# s16_panel_1.net
KiCad netlist of a schematic drawn in EAGLE
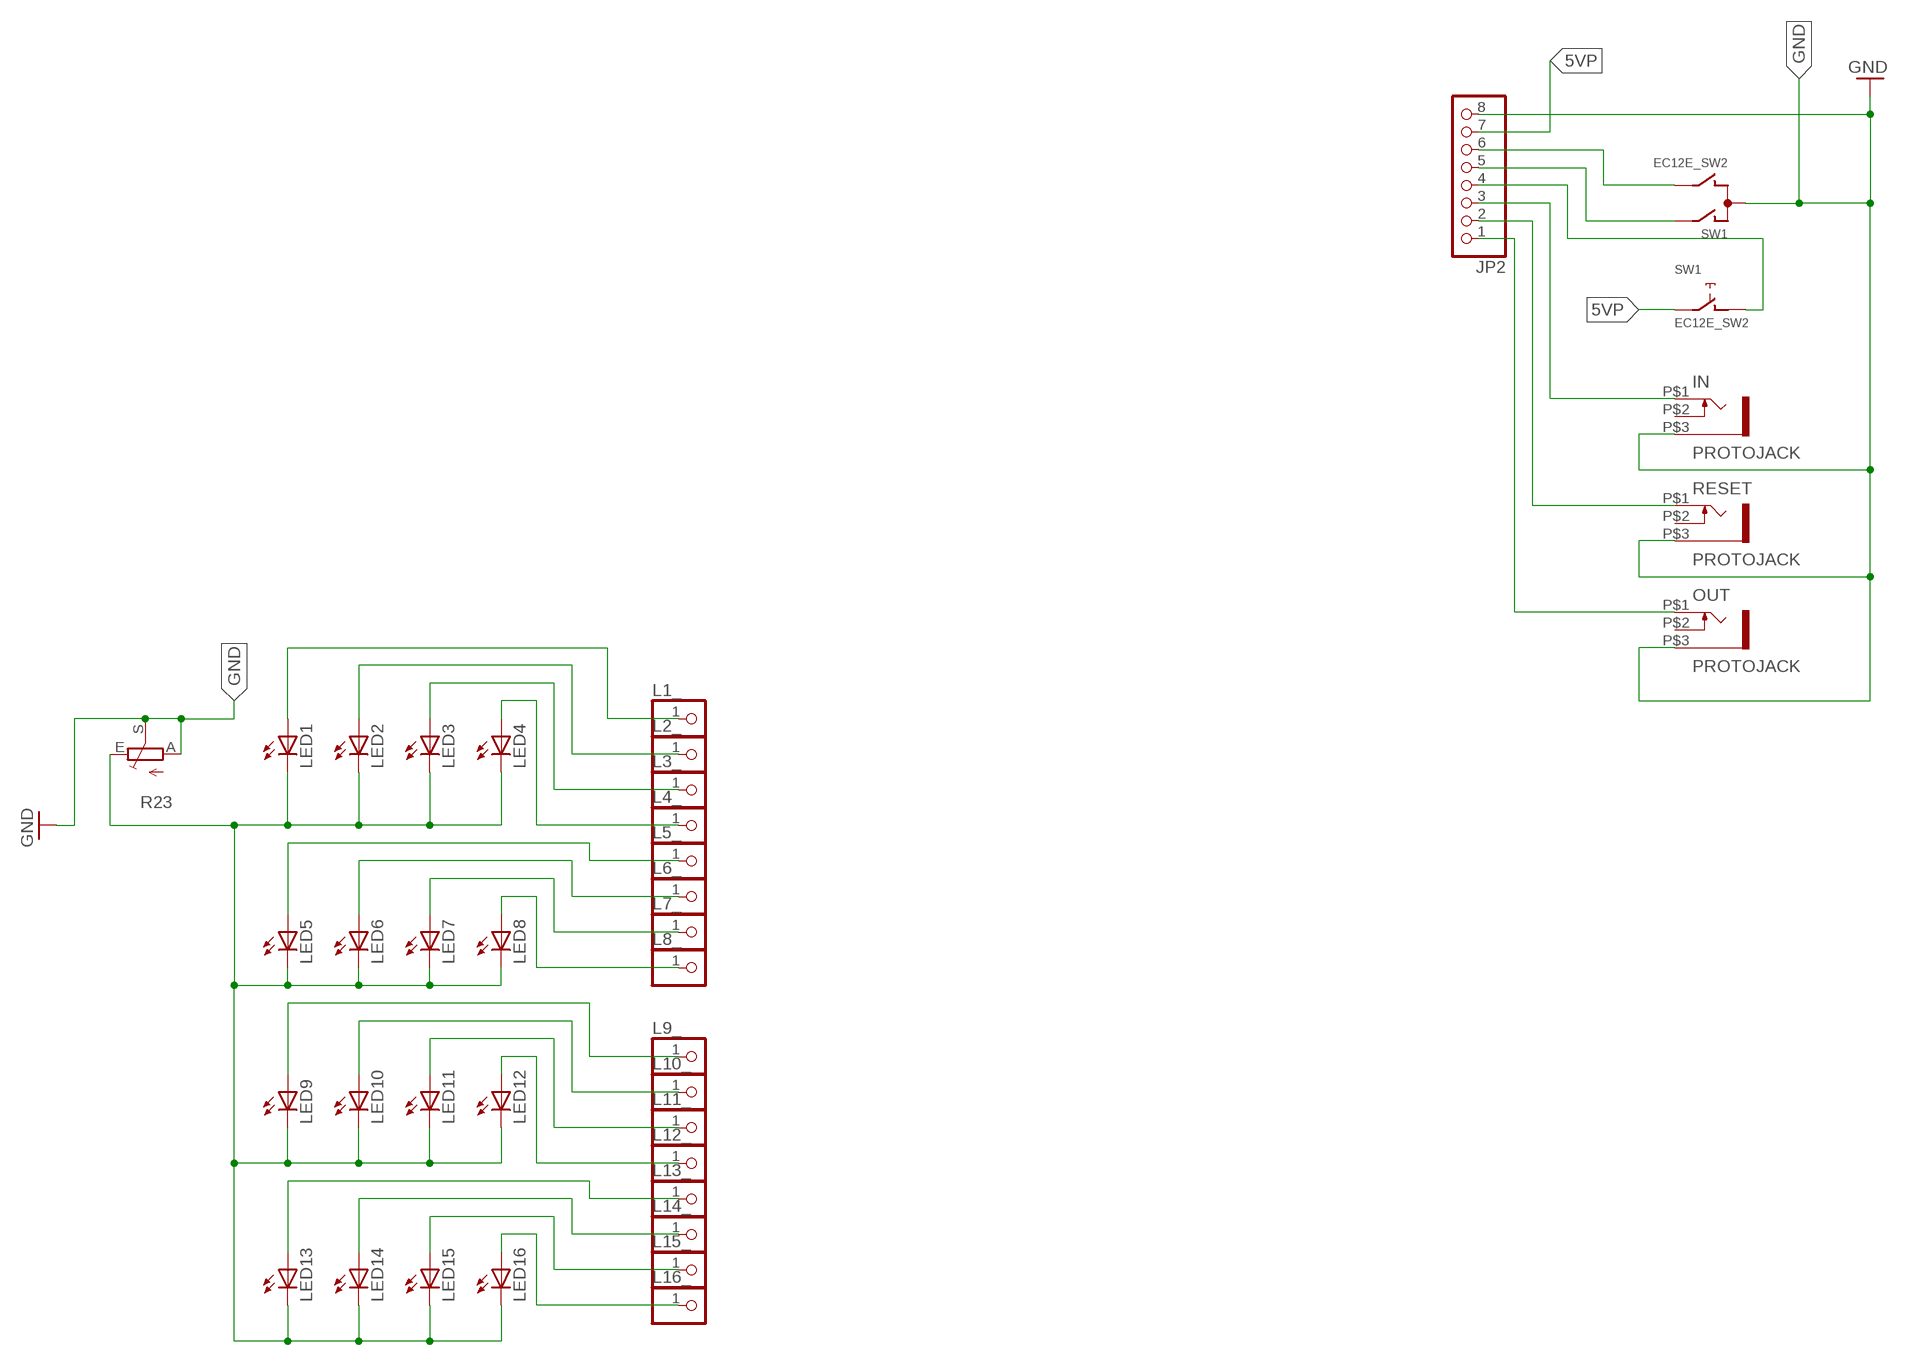
[diagram p0: schematic, sheet 1]

(export (version "E")
  (design (tool "Eeschema 10.0.6"))
  (components
    (comp (ref "IN")
      (value "PROTOJACK")
      (footprint "eagle-import:PROTOJACK")
      (libsource (lib "eagle-import") (part "PROTOJACK"))
    )
    (comp (ref "JP2")
      (value "PINHD-1X8BIG")
      (footprint "eagle-import:1X08-BIG")
      (libsource (lib "eagle-import") (part "PINHD-1X8BIG"))
    )
    (comp (ref "L1_")
      (value "PINHD-1X1")
      (footprint "eagle-import:1X01")
      (libsource (lib "eagle-import") (part "PINHD-1X1"))
    )
    (comp (ref "L2_")
      (value "PINHD-1X1")
      (footprint "eagle-import:1X01")
      (libsource (lib "eagle-import") (part "PINHD-1X1"))
    )
    (comp (ref "L3_")
      (value "PINHD-1X1")
      (footprint "eagle-import:1X01")
      (libsource (lib "eagle-import") (part "PINHD-1X1"))
    )
    (comp (ref "L4_")
      (value "PINHD-1X1")
      (footprint "eagle-import:1X01")
      (libsource (lib "eagle-import") (part "PINHD-1X1"))
    )
    (comp (ref "L5_")
      (value "PINHD-1X1")
      (footprint "eagle-import:1X01")
      (libsource (lib "eagle-import") (part "PINHD-1X1"))
    )
    (comp (ref "L6_")
      (value "PINHD-1X1")
      (footprint "eagle-import:1X01")
      (libsource (lib "eagle-import") (part "PINHD-1X1"))
    )
    (comp (ref "L7_")
      (value "PINHD-1X1")
      (footprint "eagle-import:1X01")
      (libsource (lib "eagle-import") (part "PINHD-1X1"))
    )
    (comp (ref "L8_")
      (value "PINHD-1X1")
      (footprint "eagle-import:1X01")
      (libsource (lib "eagle-import") (part "PINHD-1X1"))
    )
    (comp (ref "L9_")
      (value "PINHD-1X1")
      (footprint "eagle-import:1X01")
      (libsource (lib "eagle-import") (part "PINHD-1X1"))
    )
    (comp (ref "L10_")
      (value "PINHD-1X1")
      (footprint "eagle-import:1X01")
      (libsource (lib "eagle-import") (part "PINHD-1X1"))
    )
    (comp (ref "L11_")
      (value "PINHD-1X1")
      (footprint "eagle-import:1X01")
      (libsource (lib "eagle-import") (part "PINHD-1X1"))
    )
    (comp (ref "L12_")
      (value "PINHD-1X1")
      (footprint "eagle-import:1X01")
      (libsource (lib "eagle-import") (part "PINHD-1X1"))
    )
    (comp (ref "L13_")
      (value "PINHD-1X1")
      (footprint "eagle-import:1X01")
      (libsource (lib "eagle-import") (part "PINHD-1X1"))
    )
    (comp (ref "L14_")
      (value "PINHD-1X1")
      (footprint "eagle-import:1X01")
      (libsource (lib "eagle-import") (part "PINHD-1X1"))
    )
    (comp (ref "L15_")
      (value "PINHD-1X1")
      (footprint "eagle-import:1X01")
      (libsource (lib "eagle-import") (part "PINHD-1X1"))
    )
    (comp (ref "L16_")
      (value "PINHD-1X1")
      (footprint "eagle-import:1X01")
      (libsource (lib "eagle-import") (part "PINHD-1X1"))
    )
    (comp (ref "LED1")
      (value "LED3MM")
      (footprint "eagle-import:LED3MM")
      (libsource (lib "eagle-import") (part "LED3MM"))
    )
    (comp (ref "LED2")
      (value "LED3MM")
      (footprint "eagle-import:LED3MM")
      (libsource (lib "eagle-import") (part "LED3MM"))
    )
    (comp (ref "LED3")
      (value "LED3MM")
      (footprint "eagle-import:LED3MM")
      (libsource (lib "eagle-import") (part "LED3MM"))
    )
    (comp (ref "LED4")
      (value "LED3MM")
      (footprint "eagle-import:LED3MM")
      (libsource (lib "eagle-import") (part "LED3MM"))
    )
    (comp (ref "LED5")
      (value "LED3MM")
      (footprint "eagle-import:LED3MM")
      (libsource (lib "eagle-import") (part "LED3MM"))
    )
    (comp (ref "LED6")
      (value "LED3MM")
      (footprint "eagle-import:LED3MM")
      (libsource (lib "eagle-import") (part "LED3MM"))
    )
    (comp (ref "LED7")
      (value "LED3MM")
      (footprint "eagle-import:LED3MM")
      (libsource (lib "eagle-import") (part "LED3MM"))
    )
    (comp (ref "LED8")
      (value "LED3MM")
      (footprint "eagle-import:LED3MM")
      (libsource (lib "eagle-import") (part "LED3MM"))
    )
    (comp (ref "LED9")
      (value "LED3MM")
      (footprint "eagle-import:LED3MM")
      (libsource (lib "eagle-import") (part "LED3MM"))
    )
    (comp (ref "LED10")
      (value "LED3MM")
      (footprint "eagle-import:LED3MM")
      (libsource (lib "eagle-import") (part "LED3MM"))
    )
    (comp (ref "LED11")
      (value "LED3MM")
      (footprint "eagle-import:LED3MM")
      (libsource (lib "eagle-import") (part "LED3MM"))
    )
    (comp (ref "LED12")
      (value "LED3MM")
      (footprint "eagle-import:LED3MM")
      (libsource (lib "eagle-import") (part "LED3MM"))
    )
    (comp (ref "LED13")
      (value "LED3MM")
      (footprint "eagle-import:LED3MM")
      (libsource (lib "eagle-import") (part "LED3MM"))
    )
    (comp (ref "LED14")
      (value "LED3MM")
      (footprint "eagle-import:LED3MM")
      (libsource (lib "eagle-import") (part "LED3MM"))
    )
    (comp (ref "LED15")
      (value "LED3MM")
      (footprint "eagle-import:LED3MM")
      (libsource (lib "eagle-import") (part "LED3MM"))
    )
    (comp (ref "LED16")
      (value "LED3MM")
      (footprint "eagle-import:LED3MM")
      (libsource (lib "eagle-import") (part "LED3MM"))
    )
    (comp (ref "OUT")
      (value "PROTOJACK")
      (footprint "eagle-import:PROTOJACK")
      (libsource (lib "eagle-import") (part "PROTOJACK"))
    )
    (comp (ref "R23")
      (value "TRIM_EU-RJ9W")
      (footprint "eagle-import:RJ9W")
      (libsource (lib "eagle-import") (part "TRIM_EU-RJ9W"))
    )
    (comp (ref "RESET")
      (value "PROTOJACK")
      (footprint "eagle-import:PROTOJACK")
      (libsource (lib "eagle-import") (part "PROTOJACK"))
    )
    (comp (ref "SW1")
      (value "EC12E_SW2")
      (footprint "eagle-import:ALPS_EC12E_SW_NOSUPPORT")
      (libsource (lib "eagle-import") (part "EC12E_SW2"))
    )
  )
  (nets
    (net (code "1") (name "5VP") (class "Default")
      (node (ref "JP2") (pin "7") (pinfunction "7_7") (pintype "passive"))
      (node (ref "SW1") (pin "E") (pinfunction "2_E") (pintype "passive"))
    )
    (net (code "2") (name "GND") (class "Default")
      (node (ref "IN") (pin "P$3") (pinfunction "1_P$3") (pintype "passive"))
      (node (ref "JP2") (pin "8") (pinfunction "8_8") (pintype "passive"))
      (node (ref "OUT") (pin "P$3") (pinfunction "1_P$3") (pintype "passive"))
      (node (ref "R23") (pin "A") (pinfunction "A_A") (pintype "passive"))
      (node (ref "R23") (pin "S") (pinfunction "S_S") (pintype "passive"))
      (node (ref "RESET") (pin "P$3") (pinfunction "1_P$3") (pintype "passive"))
      (node (ref "SW1") (pin "C") (pinfunction "C_C") (pintype "passive"))
    )
    (net (code "3") (name "Net-(IN-2)") (class "Default")
      (node (ref "IN") (pin "P$1") (pinfunction "2_P$1") (pintype "passive"))
      (node (ref "JP2") (pin "3") (pinfunction "3_3") (pintype "passive"))
    )
    (net (code "4") (name "Net-(JP2-Pad5)") (class "Default")
      (node (ref "JP2") (pin "5") (pinfunction "5_5") (pintype "passive"))
      (node (ref "SW1") (pin "A") (pinfunction "A_A") (pintype "passive"))
    )
    (net (code "5") (name "Net-(JP2-Pad6)") (class "Default")
      (node (ref "JP2") (pin "6") (pinfunction "6_6") (pintype "passive"))
      (node (ref "SW1") (pin "B") (pinfunction "B_B") (pintype "passive"))
    )
    (net (code "6") (name "Net-(L1_-Pad1)") (class "Default")
      (node (ref "L1_") (pin "1") (pinfunction "1_1") (pintype "passive"))
      (node (ref "LED1") (pin "A") (pinfunction "A_A") (pintype "passive"))
    )
    (net (code "7") (name "Net-(L2_-Pad1)") (class "Default")
      (node (ref "L2_") (pin "1") (pinfunction "1_1") (pintype "passive"))
      (node (ref "LED2") (pin "A") (pinfunction "A_A") (pintype "passive"))
    )
    (net (code "8") (name "Net-(L3_-Pad1)") (class "Default")
      (node (ref "L3_") (pin "1") (pinfunction "1_1") (pintype "passive"))
      (node (ref "LED3") (pin "A") (pinfunction "A_A") (pintype "passive"))
    )
    (net (code "9") (name "Net-(L4_-Pad1)") (class "Default")
      (node (ref "L4_") (pin "1") (pinfunction "1_1") (pintype "passive"))
      (node (ref "LED4") (pin "A") (pinfunction "A_A") (pintype "passive"))
    )
    (net (code "10") (name "Net-(L5_-Pad1)") (class "Default")
      (node (ref "L5_") (pin "1") (pinfunction "1_1") (pintype "passive"))
      (node (ref "LED5") (pin "A") (pinfunction "A_A") (pintype "passive"))
    )
    (net (code "11") (name "Net-(L6_-Pad1)") (class "Default")
      (node (ref "L6_") (pin "1") (pinfunction "1_1") (pintype "passive"))
      (node (ref "LED6") (pin "A") (pinfunction "A_A") (pintype "passive"))
    )
    (net (code "12") (name "Net-(L7_-Pad1)") (class "Default")
      (node (ref "L7_") (pin "1") (pinfunction "1_1") (pintype "passive"))
      (node (ref "LED7") (pin "A") (pinfunction "A_A") (pintype "passive"))
    )
    (net (code "13") (name "Net-(L8_-Pad1)") (class "Default")
      (node (ref "L8_") (pin "1") (pinfunction "1_1") (pintype "passive"))
      (node (ref "LED8") (pin "A") (pinfunction "A_A") (pintype "passive"))
    )
    (net (code "14") (name "Net-(L9_-Pad1)") (class "Default")
      (node (ref "L9_") (pin "1") (pinfunction "1_1") (pintype "passive"))
      (node (ref "LED9") (pin "A") (pinfunction "A_A") (pintype "passive"))
    )
    (net (code "15") (name "Net-(L10_-Pad1)") (class "Default")
      (node (ref "L10_") (pin "1") (pinfunction "1_1") (pintype "passive"))
      (node (ref "LED10") (pin "A") (pinfunction "A_A") (pintype "passive"))
    )
    (net (code "16") (name "Net-(L11_-Pad1)") (class "Default")
      (node (ref "L11_") (pin "1") (pinfunction "1_1") (pintype "passive"))
      (node (ref "LED11") (pin "A") (pinfunction "A_A") (pintype "passive"))
    )
    (net (code "17") (name "Net-(L12_-Pad1)") (class "Default")
      (node (ref "L12_") (pin "1") (pinfunction "1_1") (pintype "passive"))
      (node (ref "LED12") (pin "A") (pinfunction "A_A") (pintype "passive"))
    )
    (net (code "18") (name "Net-(L13_-Pad1)") (class "Default")
      (node (ref "L13_") (pin "1") (pinfunction "1_1") (pintype "passive"))
      (node (ref "LED13") (pin "A") (pinfunction "A_A") (pintype "passive"))
    )
    (net (code "19") (name "Net-(L14_-Pad1)") (class "Default")
      (node (ref "L14_") (pin "1") (pinfunction "1_1") (pintype "passive"))
      (node (ref "LED14") (pin "A") (pinfunction "A_A") (pintype "passive"))
    )
    (net (code "20") (name "Net-(L15_-Pad1)") (class "Default")
      (node (ref "L15_") (pin "1") (pinfunction "1_1") (pintype "passive"))
      (node (ref "LED15") (pin "A") (pinfunction "A_A") (pintype "passive"))
    )
    (net (code "21") (name "Net-(L16_-Pad1)") (class "Default")
      (node (ref "L16_") (pin "1") (pinfunction "1_1") (pintype "passive"))
      (node (ref "LED16") (pin "A") (pinfunction "A_A") (pintype "passive"))
    )
    (net (code "22") (name "Net-(LED1-C)") (class "Default")
      (node (ref "LED1") (pin "K") (pinfunction "C_K") (pintype "passive"))
      (node (ref "LED10") (pin "K") (pinfunction "C_K") (pintype "passive"))
      (node (ref "LED11") (pin "K") (pinfunction "C_K") (pintype "passive"))
      (node (ref "LED12") (pin "K") (pinfunction "C_K") (pintype "passive"))
      (node (ref "LED13") (pin "K") (pinfunction "C_K") (pintype "passive"))
      (node (ref "LED14") (pin "K") (pinfunction "C_K") (pintype "passive"))
      (node (ref "LED15") (pin "K") (pinfunction "C_K") (pintype "passive"))
      (node (ref "LED16") (pin "K") (pinfunction "C_K") (pintype "passive"))
      (node (ref "LED2") (pin "K") (pinfunction "C_K") (pintype "passive"))
      (node (ref "LED3") (pin "K") (pinfunction "C_K") (pintype "passive"))
      (node (ref "LED4") (pin "K") (pinfunction "C_K") (pintype "passive"))
      (node (ref "LED5") (pin "K") (pinfunction "C_K") (pintype "passive"))
      (node (ref "LED6") (pin "K") (pinfunction "C_K") (pintype "passive"))
      (node (ref "LED7") (pin "K") (pinfunction "C_K") (pintype "passive"))
      (node (ref "LED8") (pin "K") (pinfunction "C_K") (pintype "passive"))
      (node (ref "LED9") (pin "K") (pinfunction "C_K") (pintype "passive"))
      (node (ref "R23") (pin "E") (pinfunction "E_E") (pintype "passive"))
    )
    (net (code "23") (name "Net-(OUT-2)") (class "Default")
      (node (ref "JP2") (pin "1") (pinfunction "1_1") (pintype "passive"))
      (node (ref "OUT") (pin "P$1") (pinfunction "2_P$1") (pintype "passive"))
    )
    (net (code "24") (name "Net-(RESET-2)") (class "Default")
      (node (ref "JP2") (pin "2") (pinfunction "2_2") (pintype "passive"))
      (node (ref "RESET") (pin "P$1") (pinfunction "2_P$1") (pintype "passive"))
    )
    (net (code "25") (name "Net-(SW1B-1)") (class "Default")
      (node (ref "JP2") (pin "4") (pinfunction "4_4") (pintype "passive"))
      (node (ref "SW1") (pin "D") (pinfunction "1_D") (pintype "passive"))
    )
    (net (code "26") (name "unconnected-(IN-3-PadP$2)") (class "Default")
      (node (ref "IN") (pin "P$2") (pinfunction "3_P$2") (pintype "passive"))
    )
    (net (code "27") (name "unconnected-(OUT-3-PadP$2)") (class "Default")
      (node (ref "OUT") (pin "P$2") (pinfunction "3_P$2") (pintype "passive"))
    )
    (net (code "28") (name "unconnected-(RESET-3-PadP$2)") (class "Default")
      (node (ref "RESET") (pin "P$2") (pinfunction "3_P$2") (pintype "passive"))
    )
  )
)
